# top-board.net
KiCad netlist of a schematic drawn in Altium Designer
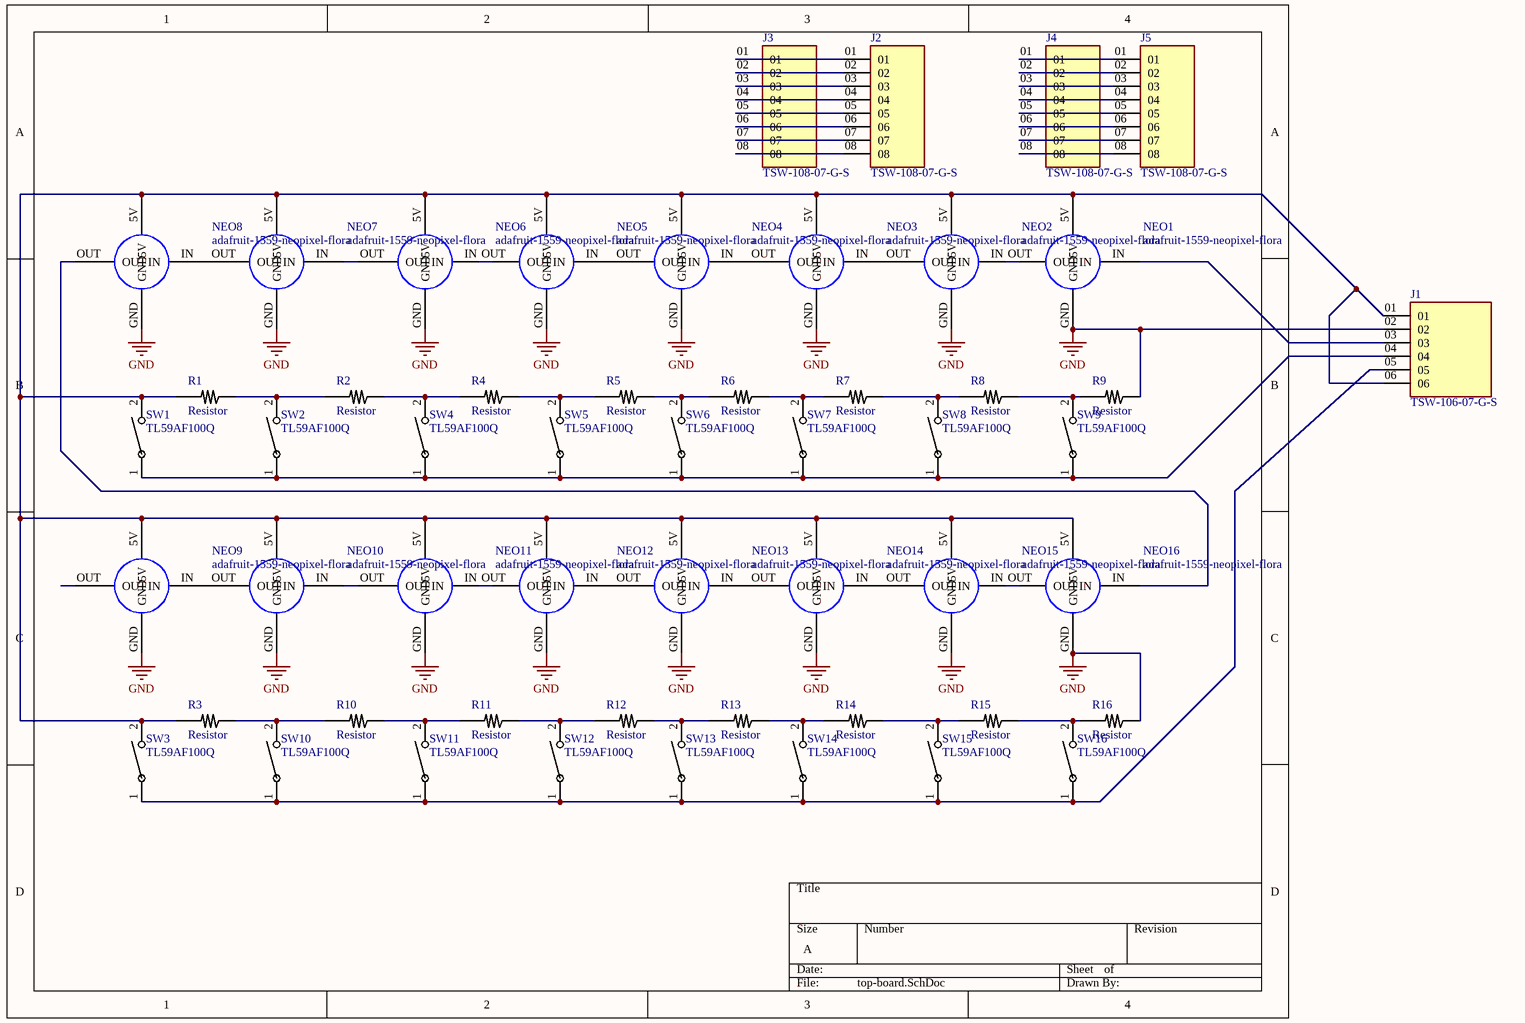
[diagram p0: top-board.SchDoc]

(export (version "E")
  (design (tool "Eeschema 10.0.6"))
  (components
    (comp (ref "J1")
      (value "TSW-106-07-G-S")
      (footprint "SAMTEC_TSW-106-07-G-S")
      (fields (field (name "MF") "Samtec Inc."))
      (libsource (lib "SchlibLafe") (part "TSW-106-07-G-S"))
    )
    (comp (ref "J2")
      (value "TSW-108-07-G-S")
      (footprint "SAMTEC_TSW-108-07-G-S")
      (description "TSW - Samtec 2.54mm Pin Header 10.92mm Overall Pin Length (07) - Fast Stock")
      (fields (field (name "MF") "Samtec Inc."))
      (libsource (lib "SchlibLafe") (part "TSW-108-07-G-S"))
    )
    (comp (ref "J3")
      (value "TSW-108-07-G-S")
      (footprint "SAMTEC_TSW-108-07-G-S")
      (description "TSW - Samtec 2.54mm Pin Header 10.92mm Overall Pin Length (07) - Fast Stock")
      (fields (field (name "MF") "Samtec Inc."))
      (libsource (lib "SchlibLafe") (part "TSW-108-07-G-S"))
    )
    (comp (ref "J4")
      (value "TSW-108-07-G-S")
      (footprint "SAMTEC_TSW-108-07-G-S")
      (description "TSW - Samtec 2.54mm Pin Header 10.92mm Overall Pin Length (07) - Fast Stock")
      (fields (field (name "MF") "Samtec Inc."))
      (libsource (lib "SchlibLafe") (part "TSW-108-07-G-S"))
    )
    (comp (ref "J5")
      (value "TSW-108-07-G-S")
      (footprint "SAMTEC_TSW-108-07-G-S")
      (description "TSW - Samtec 2.54mm Pin Header 10.92mm Overall Pin Length (07) - Fast Stock")
      (fields (field (name "MF") "Samtec Inc."))
      (libsource (lib "SchlibLafe") (part "TSW-108-07-G-S"))
    )
    (comp (ref "NEO1")
      (value "adafruit-1559-neopixel-flora")
      (footprint "adafruit-1559-neopixel-flora")
      (libsource (lib "SchlibLafe") (part "adafruit-1559-neopixel-flora"))
    )
    (comp (ref "NEO2")
      (value "adafruit-1559-neopixel-flora")
      (footprint "adafruit-1559-neopixel-flora")
      (libsource (lib "SchlibLafe") (part "adafruit-1559-neopixel-flora"))
    )
    (comp (ref "NEO3")
      (value "adafruit-1559-neopixel-flora")
      (footprint "adafruit-1559-neopixel-flora")
      (libsource (lib "SchlibLafe") (part "adafruit-1559-neopixel-flora"))
    )
    (comp (ref "NEO4")
      (value "adafruit-1559-neopixel-flora")
      (footprint "adafruit-1559-neopixel-flora")
      (libsource (lib "SchlibLafe") (part "adafruit-1559-neopixel-flora"))
    )
    (comp (ref "NEO5")
      (value "adafruit-1559-neopixel-flora")
      (footprint "adafruit-1559-neopixel-flora")
      (libsource (lib "SchlibLafe") (part "adafruit-1559-neopixel-flora"))
    )
    (comp (ref "NEO6")
      (value "adafruit-1559-neopixel-flora")
      (footprint "adafruit-1559-neopixel-flora")
      (libsource (lib "SchlibLafe") (part "adafruit-1559-neopixel-flora"))
    )
    (comp (ref "NEO7")
      (value "adafruit-1559-neopixel-flora")
      (footprint "adafruit-1559-neopixel-flora")
      (libsource (lib "SchlibLafe") (part "adafruit-1559-neopixel-flora"))
    )
    (comp (ref "NEO8")
      (value "adafruit-1559-neopixel-flora")
      (footprint "adafruit-1559-neopixel-flora")
      (libsource (lib "SchlibLafe") (part "adafruit-1559-neopixel-flora"))
    )
    (comp (ref "NEO9")
      (value "adafruit-1559-neopixel-flora")
      (footprint "adafruit-1559-neopixel-flora")
      (libsource (lib "SchlibLafe") (part "adafruit-1559-neopixel-flora"))
    )
    (comp (ref "NEO10")
      (value "adafruit-1559-neopixel-flora")
      (footprint "adafruit-1559-neopixel-flora")
      (libsource (lib "SchlibLafe") (part "adafruit-1559-neopixel-flora"))
    )
    (comp (ref "NEO11")
      (value "adafruit-1559-neopixel-flora")
      (footprint "adafruit-1559-neopixel-flora")
      (libsource (lib "SchlibLafe") (part "adafruit-1559-neopixel-flora"))
    )
    (comp (ref "NEO12")
      (value "adafruit-1559-neopixel-flora")
      (footprint "adafruit-1559-neopixel-flora")
      (libsource (lib "SchlibLafe") (part "adafruit-1559-neopixel-flora"))
    )
    (comp (ref "NEO13")
      (value "adafruit-1559-neopixel-flora")
      (footprint "adafruit-1559-neopixel-flora")
      (libsource (lib "SchlibLafe") (part "adafruit-1559-neopixel-flora"))
    )
    (comp (ref "NEO14")
      (value "adafruit-1559-neopixel-flora")
      (footprint "adafruit-1559-neopixel-flora")
      (libsource (lib "SchlibLafe") (part "adafruit-1559-neopixel-flora"))
    )
    (comp (ref "NEO15")
      (value "adafruit-1559-neopixel-flora")
      (footprint "adafruit-1559-neopixel-flora")
      (libsource (lib "SchlibLafe") (part "adafruit-1559-neopixel-flora"))
    )
    (comp (ref "NEO16")
      (value "adafruit-1559-neopixel-flora")
      (footprint "adafruit-1559-neopixel-flora")
      (libsource (lib "SchlibLafe") (part "adafruit-1559-neopixel-flora"))
    )
    (comp (ref "R1")
      (value "Resistor")
      (footprint "thruhole resistor")
      (libsource (lib "SchlibLafe") (part "Resistor"))
    )
    (comp (ref "R2")
      (value "Resistor")
      (footprint "thruhole resistor")
      (libsource (lib "SchlibLafe") (part "Resistor"))
    )
    (comp (ref "R3")
      (value "Resistor")
      (footprint "thruhole resistor")
      (libsource (lib "SchlibLafe") (part "Resistor"))
    )
    (comp (ref "R4")
      (value "Resistor")
      (footprint "thruhole resistor")
      (libsource (lib "SchlibLafe") (part "Resistor"))
    )
    (comp (ref "R5")
      (value "Resistor")
      (footprint "thruhole resistor")
      (libsource (lib "SchlibLafe") (part "Resistor"))
    )
    (comp (ref "R6")
      (value "Resistor")
      (footprint "thruhole resistor")
      (libsource (lib "SchlibLafe") (part "Resistor"))
    )
    (comp (ref "R7")
      (value "Resistor")
      (footprint "thruhole resistor")
      (libsource (lib "SchlibLafe") (part "Resistor"))
    )
    (comp (ref "R8")
      (value "Resistor")
      (footprint "thruhole resistor")
      (libsource (lib "SchlibLafe") (part "Resistor"))
    )
    (comp (ref "R9")
      (value "Resistor")
      (footprint "thruhole resistor")
      (libsource (lib "SchlibLafe") (part "Resistor"))
    )
    (comp (ref "R10")
      (value "Resistor")
      (footprint "thruhole resistor")
      (libsource (lib "SchlibLafe") (part "Resistor"))
    )
    (comp (ref "R11")
      (value "Resistor")
      (footprint "thruhole resistor")
      (libsource (lib "SchlibLafe") (part "Resistor"))
    )
    (comp (ref "R12")
      (value "Resistor")
      (footprint "thruhole resistor")
      (libsource (lib "SchlibLafe") (part "Resistor"))
    )
    (comp (ref "R13")
      (value "Resistor")
      (footprint "thruhole resistor")
      (libsource (lib "SchlibLafe") (part "Resistor"))
    )
    (comp (ref "R14")
      (value "Resistor")
      (footprint "thruhole resistor")
      (libsource (lib "SchlibLafe") (part "Resistor"))
    )
    (comp (ref "R15")
      (value "Resistor")
      (footprint "thruhole resistor")
      (libsource (lib "SchlibLafe") (part "Resistor"))
    )
    (comp (ref "R16")
      (value "Resistor")
      (footprint "thruhole resistor")
      (libsource (lib "SchlibLafe") (part "Resistor"))
    )
    (comp (ref "SW1")
      (value "TL59AF100Q")
      (footprint "SW_TL59AF100Q_EWI")
      (description "No Description Available")
      (fields (field (name "COPYRIGHT") "Copyright (C) 2024 Ultra Librarian. All rights reserved."))
      (libsource (lib "SchlibLafe") (part "TL59AF100Q"))
    )
    (comp (ref "SW2")
      (value "TL59AF100Q")
      (footprint "SW_TL59AF100Q_EWI")
      (description "No Description Available")
      (fields (field (name "COPYRIGHT") "Copyright (C) 2024 Ultra Librarian. All rights reserved."))
      (libsource (lib "SchlibLafe") (part "TL59AF100Q"))
    )
    (comp (ref "SW3")
      (value "TL59AF100Q")
      (footprint "SW_TL59AF100Q_EWI")
      (description "No Description Available")
      (fields (field (name "COPYRIGHT") "Copyright (C) 2024 Ultra Librarian. All rights reserved."))
      (libsource (lib "SchlibLafe") (part "TL59AF100Q"))
    )
    (comp (ref "SW4")
      (value "TL59AF100Q")
      (footprint "SW_TL59AF100Q_EWI")
      (description "No Description Available")
      (fields (field (name "COPYRIGHT") "Copyright (C) 2024 Ultra Librarian. All rights reserved."))
      (libsource (lib "SchlibLafe") (part "TL59AF100Q"))
    )
    (comp (ref "SW5")
      (value "TL59AF100Q")
      (footprint "SW_TL59AF100Q_EWI")
      (description "No Description Available")
      (fields (field (name "COPYRIGHT") "Copyright (C) 2024 Ultra Librarian. All rights reserved."))
      (libsource (lib "SchlibLafe") (part "TL59AF100Q"))
    )
    (comp (ref "SW6")
      (value "TL59AF100Q")
      (footprint "SW_TL59AF100Q_EWI")
      (description "No Description Available")
      (fields (field (name "COPYRIGHT") "Copyright (C) 2024 Ultra Librarian. All rights reserved."))
      (libsource (lib "SchlibLafe") (part "TL59AF100Q"))
    )
    (comp (ref "SW7")
      (value "TL59AF100Q")
      (footprint "SW_TL59AF100Q_EWI")
      (description "No Description Available")
      (fields (field (name "COPYRIGHT") "Copyright (C) 2024 Ultra Librarian. All rights reserved."))
      (libsource (lib "SchlibLafe") (part "TL59AF100Q"))
    )
    (comp (ref "SW8")
      (value "TL59AF100Q")
      (footprint "SW_TL59AF100Q_EWI")
      (description "No Description Available")
      (fields (field (name "COPYRIGHT") "Copyright (C) 2024 Ultra Librarian. All rights reserved."))
      (libsource (lib "SchlibLafe") (part "TL59AF100Q"))
    )
    (comp (ref "SW9")
      (value "TL59AF100Q")
      (footprint "SW_TL59AF100Q_EWI")
      (description "No Description Available")
      (fields (field (name "COPYRIGHT") "Copyright (C) 2024 Ultra Librarian. All rights reserved."))
      (libsource (lib "SchlibLafe") (part "TL59AF100Q"))
    )
    (comp (ref "SW10")
      (value "TL59AF100Q")
      (footprint "SW_TL59AF100Q_EWI")
      (description "No Description Available")
      (fields (field (name "COPYRIGHT") "Copyright (C) 2024 Ultra Librarian. All rights reserved."))
      (libsource (lib "SchlibLafe") (part "TL59AF100Q"))
    )
    (comp (ref "SW11")
      (value "TL59AF100Q")
      (footprint "SW_TL59AF100Q_EWI")
      (description "No Description Available")
      (fields (field (name "COPYRIGHT") "Copyright (C) 2024 Ultra Librarian. All rights reserved."))
      (libsource (lib "SchlibLafe") (part "TL59AF100Q"))
    )
    (comp (ref "SW12")
      (value "TL59AF100Q")
      (footprint "SW_TL59AF100Q_EWI")
      (description "No Description Available")
      (fields (field (name "COPYRIGHT") "Copyright (C) 2024 Ultra Librarian. All rights reserved."))
      (libsource (lib "SchlibLafe") (part "TL59AF100Q"))
    )
    (comp (ref "SW13")
      (value "TL59AF100Q")
      (footprint "SW_TL59AF100Q_EWI")
      (description "No Description Available")
      (fields (field (name "COPYRIGHT") "Copyright (C) 2024 Ultra Librarian. All rights reserved."))
      (libsource (lib "SchlibLafe") (part "TL59AF100Q"))
    )
    (comp (ref "SW14")
      (value "TL59AF100Q")
      (footprint "SW_TL59AF100Q_EWI")
      (description "No Description Available")
      (fields (field (name "COPYRIGHT") "Copyright (C) 2024 Ultra Librarian. All rights reserved."))
      (libsource (lib "SchlibLafe") (part "TL59AF100Q"))
    )
    (comp (ref "SW15")
      (value "TL59AF100Q")
      (footprint "SW_TL59AF100Q_EWI")
      (description "No Description Available")
      (fields (field (name "COPYRIGHT") "Copyright (C) 2024 Ultra Librarian. All rights reserved."))
      (libsource (lib "SchlibLafe") (part "TL59AF100Q"))
    )
    (comp (ref "SW16")
      (value "TL59AF100Q")
      (footprint "SW_TL59AF100Q_EWI")
      (description "No Description Available")
      (fields (field (name "COPYRIGHT") "Copyright (C) 2024 Ultra Librarian. All rights reserved."))
      (libsource (lib "SchlibLafe") (part "TL59AF100Q"))
    )
  )
  (nets
    (net (code "1") (name "GND") (class "Default")
      (node (ref "J1") (pin "02") (pinfunction "02_02") (pintype "passive"))
      (node (ref "NEO1") (pin "GND") (pinfunction "GND_GND") (pintype "passive"))
      (node (ref "NEO10") (pin "GND") (pinfunction "GND_GND") (pintype "passive"))
      (node (ref "NEO11") (pin "GND") (pinfunction "GND_GND") (pintype "passive"))
      (node (ref "NEO12") (pin "GND") (pinfunction "GND_GND") (pintype "passive"))
      (node (ref "NEO13") (pin "GND") (pinfunction "GND_GND") (pintype "passive"))
      (node (ref "NEO14") (pin "GND") (pinfunction "GND_GND") (pintype "passive"))
      (node (ref "NEO15") (pin "GND") (pinfunction "GND_GND") (pintype "passive"))
      (node (ref "NEO16") (pin "GND") (pinfunction "GND_GND") (pintype "passive"))
      (node (ref "NEO2") (pin "GND") (pinfunction "GND_GND") (pintype "passive"))
      (node (ref "NEO3") (pin "GND") (pinfunction "GND_GND") (pintype "passive"))
      (node (ref "NEO4") (pin "GND") (pinfunction "GND_GND") (pintype "passive"))
      (node (ref "NEO5") (pin "GND") (pinfunction "GND_GND") (pintype "passive"))
      (node (ref "NEO6") (pin "GND") (pinfunction "GND_GND") (pintype "passive"))
      (node (ref "NEO7") (pin "GND") (pinfunction "GND_GND") (pintype "passive"))
      (node (ref "NEO8") (pin "GND") (pinfunction "GND_GND") (pintype "passive"))
      (node (ref "NEO9") (pin "GND") (pinfunction "GND_GND") (pintype "passive"))
      (node (ref "R16") (pin "1") (pinfunction "1_1") (pintype "passive"))
      (node (ref "R9") (pin "1") (pinfunction "1_1") (pintype "passive"))
    )
    (net (code "2") (name "Net-(J1-Pad01)") (class "Default")
      (node (ref "J1") (pin "01") (pinfunction "01_01") (pintype "passive"))
      (node (ref "J1") (pin "06") (pinfunction "06_06") (pintype "passive"))
      (node (ref "NEO1") (pin "5V") (pinfunction "5V_5V") (pintype "passive"))
      (node (ref "NEO10") (pin "5V") (pinfunction "5V_5V") (pintype "passive"))
      (node (ref "NEO11") (pin "5V") (pinfunction "5V_5V") (pintype "passive"))
      (node (ref "NEO12") (pin "5V") (pinfunction "5V_5V") (pintype "passive"))
      (node (ref "NEO13") (pin "5V") (pinfunction "5V_5V") (pintype "passive"))
      (node (ref "NEO14") (pin "5V") (pinfunction "5V_5V") (pintype "passive"))
      (node (ref "NEO15") (pin "5V") (pinfunction "5V_5V") (pintype "passive"))
      (node (ref "NEO16") (pin "5V") (pinfunction "5V_5V") (pintype "passive"))
      (node (ref "NEO2") (pin "5V") (pinfunction "5V_5V") (pintype "passive"))
      (node (ref "NEO3") (pin "5V") (pinfunction "5V_5V") (pintype "passive"))
      (node (ref "NEO4") (pin "5V") (pinfunction "5V_5V") (pintype "passive"))
      (node (ref "NEO5") (pin "5V") (pinfunction "5V_5V") (pintype "passive"))
      (node (ref "NEO6") (pin "5V") (pinfunction "5V_5V") (pintype "passive"))
      (node (ref "NEO7") (pin "5V") (pinfunction "5V_5V") (pintype "passive"))
      (node (ref "NEO8") (pin "5V") (pinfunction "5V_5V") (pintype "passive"))
      (node (ref "NEO9") (pin "5V") (pinfunction "5V_5V") (pintype "passive"))
      (node (ref "R1") (pin "2") (pinfunction "2_2") (pintype "passive"))
      (node (ref "R3") (pin "2") (pinfunction "2_2") (pintype "passive"))
      (node (ref "SW1") (pin "2") (pinfunction "2_2") (pintype "passive"))
      (node (ref "SW3") (pin "2") (pinfunction "2_2") (pintype "passive"))
    )
    (net (code "3") (name "Net-(J1-Pad03)") (class "Default")
      (node (ref "J1") (pin "03") (pinfunction "03_03") (pintype "passive"))
      (node (ref "NEO1") (pin "IN") (pinfunction "IN_IN") (pintype "passive"))
    )
    (net (code "4") (name "Net-(J1-Pad04)") (class "Default")
      (node (ref "J1") (pin "04") (pinfunction "04_04") (pintype "passive"))
      (node (ref "SW1") (pin "1") (pinfunction "1_1") (pintype "passive"))
      (node (ref "SW2") (pin "1") (pinfunction "1_1") (pintype "passive"))
      (node (ref "SW4") (pin "1") (pinfunction "1_1") (pintype "passive"))
      (node (ref "SW5") (pin "1") (pinfunction "1_1") (pintype "passive"))
      (node (ref "SW6") (pin "1") (pinfunction "1_1") (pintype "passive"))
      (node (ref "SW7") (pin "1") (pinfunction "1_1") (pintype "passive"))
      (node (ref "SW8") (pin "1") (pinfunction "1_1") (pintype "passive"))
      (node (ref "SW9") (pin "1") (pinfunction "1_1") (pintype "passive"))
    )
    (net (code "5") (name "Net-(J1-Pad05)") (class "Default")
      (node (ref "J1") (pin "05") (pinfunction "05_05") (pintype "passive"))
      (node (ref "SW10") (pin "1") (pinfunction "1_1") (pintype "passive"))
      (node (ref "SW11") (pin "1") (pinfunction "1_1") (pintype "passive"))
      (node (ref "SW12") (pin "1") (pinfunction "1_1") (pintype "passive"))
      (node (ref "SW13") (pin "1") (pinfunction "1_1") (pintype "passive"))
      (node (ref "SW14") (pin "1") (pinfunction "1_1") (pintype "passive"))
      (node (ref "SW15") (pin "1") (pinfunction "1_1") (pintype "passive"))
      (node (ref "SW16") (pin "1") (pinfunction "1_1") (pintype "passive"))
      (node (ref "SW3") (pin "1") (pinfunction "1_1") (pintype "passive"))
    )
    (net (code "6") (name "Net-(J2-Pad01)") (class "Default")
      (node (ref "J2") (pin "01") (pinfunction "01_01") (pintype "passive"))
      (node (ref "J3") (pin "01") (pinfunction "01_01") (pintype "passive"))
    )
    (net (code "7") (name "Net-(J2-Pad02)") (class "Default")
      (node (ref "J2") (pin "02") (pinfunction "02_02") (pintype "passive"))
      (node (ref "J3") (pin "02") (pinfunction "02_02") (pintype "passive"))
    )
    (net (code "8") (name "Net-(J2-Pad03)") (class "Default")
      (node (ref "J2") (pin "03") (pinfunction "03_03") (pintype "passive"))
      (node (ref "J3") (pin "03") (pinfunction "03_03") (pintype "passive"))
    )
    (net (code "9") (name "Net-(J2-Pad04)") (class "Default")
      (node (ref "J2") (pin "04") (pinfunction "04_04") (pintype "passive"))
      (node (ref "J3") (pin "04") (pinfunction "04_04") (pintype "passive"))
    )
    (net (code "10") (name "Net-(J2-Pad05)") (class "Default")
      (node (ref "J2") (pin "05") (pinfunction "05_05") (pintype "passive"))
      (node (ref "J3") (pin "05") (pinfunction "05_05") (pintype "passive"))
    )
    (net (code "11") (name "Net-(J2-Pad06)") (class "Default")
      (node (ref "J2") (pin "06") (pinfunction "06_06") (pintype "passive"))
      (node (ref "J3") (pin "06") (pinfunction "06_06") (pintype "passive"))
    )
    (net (code "12") (name "Net-(J2-Pad07)") (class "Default")
      (node (ref "J2") (pin "07") (pinfunction "07_07") (pintype "passive"))
      (node (ref "J3") (pin "07") (pinfunction "07_07") (pintype "passive"))
    )
    (net (code "13") (name "Net-(J2-Pad08)") (class "Default")
      (node (ref "J2") (pin "08") (pinfunction "08_08") (pintype "passive"))
      (node (ref "J3") (pin "08") (pinfunction "08_08") (pintype "passive"))
    )
    (net (code "14") (name "Net-(J4-Pad01)") (class "Default")
      (node (ref "J4") (pin "01") (pinfunction "01_01") (pintype "passive"))
      (node (ref "J5") (pin "01") (pinfunction "01_01") (pintype "passive"))
    )
    (net (code "15") (name "Net-(J4-Pad02)") (class "Default")
      (node (ref "J4") (pin "02") (pinfunction "02_02") (pintype "passive"))
      (node (ref "J5") (pin "02") (pinfunction "02_02") (pintype "passive"))
    )
    (net (code "16") (name "Net-(J4-Pad03)") (class "Default")
      (node (ref "J4") (pin "03") (pinfunction "03_03") (pintype "passive"))
      (node (ref "J5") (pin "03") (pinfunction "03_03") (pintype "passive"))
    )
    (net (code "17") (name "Net-(J4-Pad04)") (class "Default")
      (node (ref "J4") (pin "04") (pinfunction "04_04") (pintype "passive"))
      (node (ref "J5") (pin "04") (pinfunction "04_04") (pintype "passive"))
    )
    (net (code "18") (name "Net-(J4-Pad05)") (class "Default")
      (node (ref "J4") (pin "05") (pinfunction "05_05") (pintype "passive"))
      (node (ref "J5") (pin "05") (pinfunction "05_05") (pintype "passive"))
    )
    (net (code "19") (name "Net-(J4-Pad06)") (class "Default")
      (node (ref "J4") (pin "06") (pinfunction "06_06") (pintype "passive"))
      (node (ref "J5") (pin "06") (pinfunction "06_06") (pintype "passive"))
    )
    (net (code "20") (name "Net-(J4-Pad07)") (class "Default")
      (node (ref "J4") (pin "07") (pinfunction "07_07") (pintype "passive"))
      (node (ref "J5") (pin "07") (pinfunction "07_07") (pintype "passive"))
    )
    (net (code "21") (name "Net-(J4-Pad08)") (class "Default")
      (node (ref "J4") (pin "08") (pinfunction "08_08") (pintype "passive"))
      (node (ref "J5") (pin "08") (pinfunction "08_08") (pintype "passive"))
    )
    (net (code "22") (name "Net-(NEO1-PadOUT)") (class "Default")
      (node (ref "NEO1") (pin "OUT") (pinfunction "OUT_OUT") (pintype "passive"))
      (node (ref "NEO2") (pin "IN") (pinfunction "IN_IN") (pintype "passive"))
    )
    (net (code "23") (name "Net-(NEO2-PadOUT)") (class "Default")
      (node (ref "NEO2") (pin "OUT") (pinfunction "OUT_OUT") (pintype "passive"))
      (node (ref "NEO3") (pin "IN") (pinfunction "IN_IN") (pintype "passive"))
    )
    (net (code "24") (name "Net-(NEO3-PadOUT)") (class "Default")
      (node (ref "NEO3") (pin "OUT") (pinfunction "OUT_OUT") (pintype "passive"))
      (node (ref "NEO4") (pin "IN") (pinfunction "IN_IN") (pintype "passive"))
    )
    (net (code "25") (name "Net-(NEO4-PadOUT)") (class "Default")
      (node (ref "NEO4") (pin "OUT") (pinfunction "OUT_OUT") (pintype "passive"))
      (node (ref "NEO5") (pin "IN") (pinfunction "IN_IN") (pintype "passive"))
    )
    (net (code "26") (name "Net-(NEO5-PadOUT)") (class "Default")
      (node (ref "NEO5") (pin "OUT") (pinfunction "OUT_OUT") (pintype "passive"))
      (node (ref "NEO6") (pin "IN") (pinfunction "IN_IN") (pintype "passive"))
    )
    (net (code "27") (name "Net-(NEO6-PadOUT)") (class "Default")
      (node (ref "NEO6") (pin "OUT") (pinfunction "OUT_OUT") (pintype "passive"))
      (node (ref "NEO7") (pin "IN") (pinfunction "IN_IN") (pintype "passive"))
    )
    (net (code "28") (name "Net-(NEO7-PadOUT)") (class "Default")
      (node (ref "NEO7") (pin "OUT") (pinfunction "OUT_OUT") (pintype "passive"))
      (node (ref "NEO8") (pin "IN") (pinfunction "IN_IN") (pintype "passive"))
    )
    (net (code "29") (name "Net-(NEO10-PadIN)") (class "Default")
      (node (ref "NEO10") (pin "IN") (pinfunction "IN_IN") (pintype "passive"))
      (node (ref "NEO11") (pin "OUT") (pinfunction "OUT_OUT") (pintype "passive"))
    )
    (net (code "30") (name "Net-(NEO10-PadOUT)") (class "Default")
      (node (ref "NEO10") (pin "OUT") (pinfunction "OUT_OUT") (pintype "passive"))
      (node (ref "NEO9") (pin "IN") (pinfunction "IN_IN") (pintype "passive"))
    )
    (net (code "31") (name "Net-(NEO11-PadIN)") (class "Default")
      (node (ref "NEO11") (pin "IN") (pinfunction "IN_IN") (pintype "passive"))
      (node (ref "NEO12") (pin "OUT") (pinfunction "OUT_OUT") (pintype "passive"))
    )
    (net (code "32") (name "Net-(NEO12-PadIN)") (class "Default")
      (node (ref "NEO12") (pin "IN") (pinfunction "IN_IN") (pintype "passive"))
      (node (ref "NEO13") (pin "OUT") (pinfunction "OUT_OUT") (pintype "passive"))
    )
    (net (code "33") (name "Net-(NEO13-PadIN)") (class "Default")
      (node (ref "NEO13") (pin "IN") (pinfunction "IN_IN") (pintype "passive"))
      (node (ref "NEO14") (pin "OUT") (pinfunction "OUT_OUT") (pintype "passive"))
    )
    (net (code "34") (name "Net-(NEO14-PadIN)") (class "Default")
      (node (ref "NEO14") (pin "IN") (pinfunction "IN_IN") (pintype "passive"))
      (node (ref "NEO15") (pin "OUT") (pinfunction "OUT_OUT") (pintype "passive"))
    )
    (net (code "35") (name "Net-(NEO15-PadIN)") (class "Default")
      (node (ref "NEO15") (pin "IN") (pinfunction "IN_IN") (pintype "passive"))
      (node (ref "NEO16") (pin "OUT") (pinfunction "OUT_OUT") (pintype "passive"))
    )
    (net (code "36") (name "Net-(NEO16-PadIN)") (class "Default")
      (node (ref "NEO16") (pin "IN") (pinfunction "IN_IN") (pintype "passive"))
      (node (ref "NEO8") (pin "OUT") (pinfunction "OUT_OUT") (pintype "passive"))
    )
    (net (code "37") (name "Net-(R1-Pad1)") (class "Default")
      (node (ref "R1") (pin "1") (pinfunction "1_1") (pintype "passive"))
      (node (ref "R2") (pin "2") (pinfunction "2_2") (pintype "passive"))
      (node (ref "SW2") (pin "2") (pinfunction "2_2") (pintype "passive"))
    )
    (net (code "38") (name "Net-(R2-Pad1)") (class "Default")
      (node (ref "R2") (pin "1") (pinfunction "1_1") (pintype "passive"))
      (node (ref "R4") (pin "2") (pinfunction "2_2") (pintype "passive"))
      (node (ref "SW4") (pin "2") (pinfunction "2_2") (pintype "passive"))
    )
    (net (code "39") (name "Net-(R4-Pad1)") (class "Default")
      (node (ref "R4") (pin "1") (pinfunction "1_1") (pintype "passive"))
      (node (ref "R5") (pin "2") (pinfunction "2_2") (pintype "passive"))
      (node (ref "SW5") (pin "2") (pinfunction "2_2") (pintype "passive"))
    )
    (net (code "40") (name "Net-(R5-Pad1)") (class "Default")
      (node (ref "R5") (pin "1") (pinfunction "1_1") (pintype "passive"))
      (node (ref "R6") (pin "2") (pinfunction "2_2") (pintype "passive"))
      (node (ref "SW6") (pin "2") (pinfunction "2_2") (pintype "passive"))
    )
    (net (code "41") (name "Net-(R6-Pad1)") (class "Default")
      (node (ref "R6") (pin "1") (pinfunction "1_1") (pintype "passive"))
      (node (ref "R7") (pin "2") (pinfunction "2_2") (pintype "passive"))
      (node (ref "SW7") (pin "2") (pinfunction "2_2") (pintype "passive"))
    )
    (net (code "42") (name "Net-(R7-Pad1)") (class "Default")
      (node (ref "R7") (pin "1") (pinfunction "1_1") (pintype "passive"))
      (node (ref "R8") (pin "2") (pinfunction "2_2") (pintype "passive"))
      (node (ref "SW8") (pin "2") (pinfunction "2_2") (pintype "passive"))
    )
    (net (code "43") (name "Net-(R8-Pad1)") (class "Default")
      (node (ref "R8") (pin "1") (pinfunction "1_1") (pintype "passive"))
      (node (ref "R9") (pin "2") (pinfunction "2_2") (pintype "passive"))
      (node (ref "SW9") (pin "2") (pinfunction "2_2") (pintype "passive"))
    )
    (net (code "44") (name "Net-(R10-Pad1)") (class "Default")
      (node (ref "R10") (pin "1") (pinfunction "1_1") (pintype "passive"))
      (node (ref "R11") (pin "2") (pinfunction "2_2") (pintype "passive"))
      (node (ref "SW11") (pin "2") (pinfunction "2_2") (pintype "passive"))
    )
    (net (code "45") (name "Net-(R10-Pad2)") (class "Default")
      (node (ref "R10") (pin "2") (pinfunction "2_2") (pintype "passive"))
      (node (ref "R3") (pin "1") (pinfunction "1_1") (pintype "passive"))
      (node (ref "SW10") (pin "2") (pinfunction "2_2") (pintype "passive"))
    )
    (net (code "46") (name "Net-(R11-Pad1)") (class "Default")
      (node (ref "R11") (pin "1") (pinfunction "1_1") (pintype "passive"))
      (node (ref "R12") (pin "2") (pinfunction "2_2") (pintype "passive"))
      (node (ref "SW12") (pin "2") (pinfunction "2_2") (pintype "passive"))
    )
    (net (code "47") (name "Net-(R12-Pad1)") (class "Default")
      (node (ref "R12") (pin "1") (pinfunction "1_1") (pintype "passive"))
      (node (ref "R13") (pin "2") (pinfunction "2_2") (pintype "passive"))
      (node (ref "SW13") (pin "2") (pinfunction "2_2") (pintype "passive"))
    )
    (net (code "48") (name "Net-(R13-Pad1)") (class "Default")
      (node (ref "R13") (pin "1") (pinfunction "1_1") (pintype "passive"))
      (node (ref "R14") (pin "2") (pinfunction "2_2") (pintype "passive"))
      (node (ref "SW14") (pin "2") (pinfunction "2_2") (pintype "passive"))
    )
    (net (code "49") (name "Net-(R14-Pad1)") (class "Default")
      (node (ref "R14") (pin "1") (pinfunction "1_1") (pintype "passive"))
      (node (ref "R15") (pin "2") (pinfunction "2_2") (pintype "passive"))
      (node (ref "SW15") (pin "2") (pinfunction "2_2") (pintype "passive"))
    )
    (net (code "50") (name "Net-(R15-Pad1)") (class "Default")
      (node (ref "R15") (pin "1") (pinfunction "1_1") (pintype "passive"))
      (node (ref "R16") (pin "2") (pinfunction "2_2") (pintype "passive"))
      (node (ref "SW16") (pin "2") (pinfunction "2_2") (pintype "passive"))
    )
    (net (code "51") (name "unconnected-(NEO9-PadOUT)") (class "Default")
      (node (ref "NEO9") (pin "OUT") (pinfunction "OUT_OUT") (pintype "passive"))
    )
  )
)
